# xbee.net
KiCad netlist of a schematic drawn in EAGLE
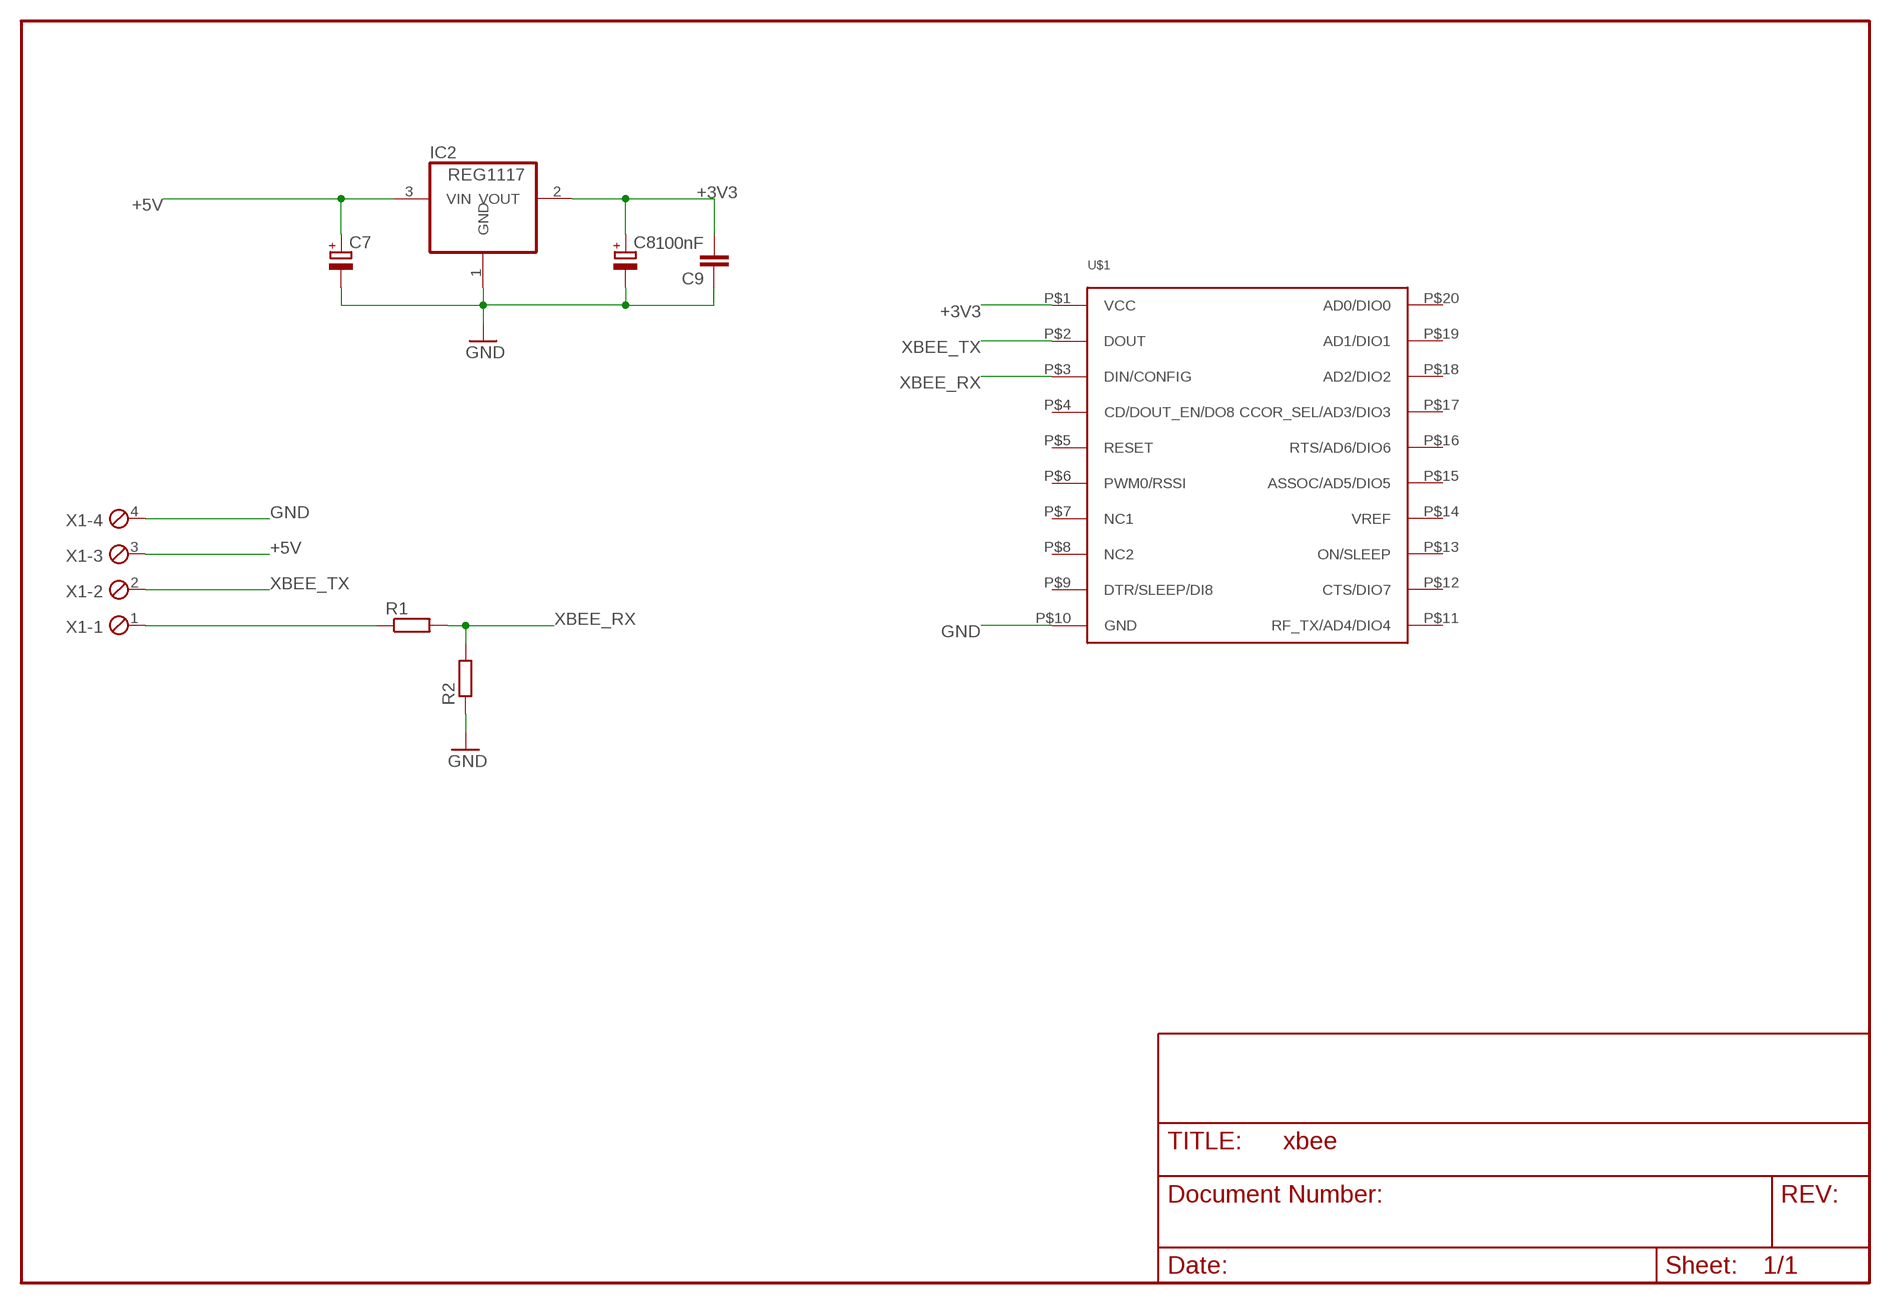
[diagram p0: schematic, sheet 1]

(export (version "E")
  (design (tool "Eeschema 10.0.6"))
  (components
    (comp (ref "C7")
      (value "CPOL-EUA/3216-18R")
      (footprint "eagle-import:A_3216-18R")
      (libsource (lib "eagle-import") (part "CPOL-EUA/3216-18R"))
    )
    (comp (ref "C8")
      (value "CPOL-EUB/3528-21R")
      (footprint "eagle-import:B_3528-21R")
      (libsource (lib "eagle-import") (part "CPOL-EUB/3528-21R"))
    )
    (comp (ref "C9")
      (value "100nF")
      (footprint "eagle-import:C0603")
      (libsource (lib "eagle-import") (part "C-EUC0603"))
    )
    (comp (ref "IC2")
      (value "REG1117")
      (footprint "eagle-import:SOT223")
      (libsource (lib "eagle-import") (part "REG1117"))
    )
    (comp (ref "R1")
      (value "R-EU_R1206W")
      (footprint "eagle-import:R1206W")
      (libsource (lib "eagle-import") (part "R-EU_R1206W"))
    )
    (comp (ref "R2")
      (value "R-EU_R1206W")
      (footprint "eagle-import:R1206W")
      (libsource (lib "eagle-import") (part "R-EU_R1206W"))
    )
    (comp (ref "U$1")
      (value "XBEEPRO")
      (footprint "eagle-import:XBEE")
      (libsource (lib "eagle-import") (part "XBEEPRO"))
    )
    (comp (ref "X1")
      (value "MPT4")
      (footprint "eagle-import:4POL254")
      (libsource (lib "eagle-import") (part "MPT4"))
    )
  )
  (nets
    (net (code "1") (name "/+3V3") (class "Default")
      (node (ref "C8") (pin "+") (pinfunction "+_+") (pintype "passive"))
      (node (ref "C9") (pin "2") (pinfunction "2_2") (pintype "passive"))
      (node (ref "IC2") (pin "2") (pinfunction "VOUT_2") (pintype "output"))
      (node (ref "U$1") (pin "P$1") (pinfunction "VCC_P$1") (pintype "bidirectional"))
    )
    (net (code "2") (name "/+5V") (class "Default")
      (node (ref "C7") (pin "+") (pinfunction "+_+") (pintype "passive"))
      (node (ref "IC2") (pin "3") (pinfunction "VIN_3") (pintype "input"))
      (node (ref "X1") (pin "3") (pinfunction "1_3") (pintype "passive"))
    )
    (net (code "3") (name "/XBEE_RX") (class "Default")
      (node (ref "R1") (pin "2") (pinfunction "2_2") (pintype "passive"))
      (node (ref "R2") (pin "2") (pinfunction "2_2") (pintype "passive"))
      (node (ref "U$1") (pin "P$3") (pinfunction "DIN/CONFIG_P$3") (pintype "bidirectional"))
    )
    (net (code "4") (name "/XBEE_TX") (class "Default")
      (node (ref "U$1") (pin "P$2") (pinfunction "DOUT_P$2") (pintype "bidirectional"))
      (node (ref "X1") (pin "2") (pinfunction "1_2") (pintype "passive"))
    )
    (net (code "5") (name "GND") (class "Default")
      (node (ref "C7") (pin "-") (pinfunction "-_-") (pintype "passive"))
      (node (ref "C8") (pin "-") (pinfunction "-_-") (pintype "passive"))
      (node (ref "C9") (pin "1") (pinfunction "1_1") (pintype "passive"))
      (node (ref "IC2") (pin "1") (pinfunction "GND_1") (pintype "power_in"))
      (node (ref "R2") (pin "1") (pinfunction "1_1") (pintype "passive"))
      (node (ref "U$1") (pin "P$10") (pinfunction "GND_P$10") (pintype "bidirectional"))
      (node (ref "X1") (pin "4") (pinfunction "1_4") (pintype "passive"))
    )
    (net (code "6") (name "Net-(R1-Pad1)") (class "Default")
      (node (ref "R1") (pin "1") (pinfunction "1_1") (pintype "passive"))
      (node (ref "X1") (pin "1") (pinfunction "1_1") (pintype "passive"))
    )
    (net (code "7") (name "unconnected-(U$1-AD0{slash}DIO0-PadP$20)") (class "Default")
      (node (ref "U$1") (pin "P$20") (pinfunction "AD0/DIO0_P$20") (pintype "bidirectional"))
    )
    (net (code "8") (name "unconnected-(U$1-AD1{slash}DIO1-PadP$19)") (class "Default")
      (node (ref "U$1") (pin "P$19") (pinfunction "AD1/DIO1_P$19") (pintype "bidirectional"))
    )
    (net (code "9") (name "unconnected-(U$1-AD2{slash}DIO2-PadP$18)") (class "Default")
      (node (ref "U$1") (pin "P$18") (pinfunction "AD2/DIO2_P$18") (pintype "bidirectional"))
    )
    (net (code "10") (name "unconnected-(U$1-ASSOC{slash}AD5{slash}DIO5-PadP$15)") (class "Default")
      (node (ref "U$1") (pin "P$15") (pinfunction "ASSOC/AD5/DIO5_P$15") (pintype "bidirectional"))
    )
    (net (code "11") (name "unconnected-(U$1-CCOR_SEL{slash}AD3{slash}DIO3-PadP$17)") (class "Default")
      (node (ref "U$1") (pin "P$17") (pinfunction "CCOR_SEL/AD3/DIO3_P$17") (pintype "bidirectional"))
    )
    (net (code "12") (name "unconnected-(U$1-CD{slash}DOUT_EN{slash}DO8-PadP$4)") (class "Default")
      (node (ref "U$1") (pin "P$4") (pinfunction "CD/DOUT_EN/DO8_P$4") (pintype "bidirectional"))
    )
    (net (code "13") (name "unconnected-(U$1-CTS{slash}DIO7-PadP$12)") (class "Default")
      (node (ref "U$1") (pin "P$12") (pinfunction "CTS/DIO7_P$12") (pintype "bidirectional"))
    )
    (net (code "14") (name "unconnected-(U$1-DTR{slash}SLEEP{slash}DI8-PadP$9)") (class "Default")
      (node (ref "U$1") (pin "P$9") (pinfunction "DTR/SLEEP/DI8_P$9") (pintype "bidirectional"))
    )
    (net (code "15") (name "unconnected-(U$1-NC1-PadP$7)") (class "Default")
      (node (ref "U$1") (pin "P$7") (pinfunction "NC1_P$7") (pintype "bidirectional"))
    )
    (net (code "16") (name "unconnected-(U$1-NC2-PadP$8)") (class "Default")
      (node (ref "U$1") (pin "P$8") (pinfunction "NC2_P$8") (pintype "bidirectional"))
    )
    (net (code "17") (name "unconnected-(U$1-ON{slash}SLEEP-PadP$13)") (class "Default")
      (node (ref "U$1") (pin "P$13") (pinfunction "ON/SLEEP_P$13") (pintype "bidirectional"))
    )
    (net (code "18") (name "unconnected-(U$1-PWM0{slash}RSSI-PadP$6)") (class "Default")
      (node (ref "U$1") (pin "P$6") (pinfunction "PWM0/RSSI_P$6") (pintype "bidirectional"))
    )
    (net (code "19") (name "unconnected-(U$1-RESET-PadP$5)") (class "Default")
      (node (ref "U$1") (pin "P$5") (pinfunction "RESET_P$5") (pintype "bidirectional"))
    )
    (net (code "20") (name "unconnected-(U$1-RF_TX{slash}AD4{slash}DIO4-PadP$11)") (class "Default")
      (node (ref "U$1") (pin "P$11") (pinfunction "RF_TX/AD4/DIO4_P$11") (pintype "bidirectional"))
    )
    (net (code "21") (name "unconnected-(U$1-RTS{slash}AD6{slash}DIO6-PadP$16)") (class "Default")
      (node (ref "U$1") (pin "P$16") (pinfunction "RTS/AD6/DIO6_P$16") (pintype "bidirectional"))
    )
    (net (code "22") (name "unconnected-(U$1-VREF-PadP$14)") (class "Default")
      (node (ref "U$1") (pin "P$14") (pinfunction "VREF_P$14") (pintype "bidirectional"))
    )
  )
)
